# sheet6_power_supply.net
KiCad netlist of a schematic drawn in Altium Designer
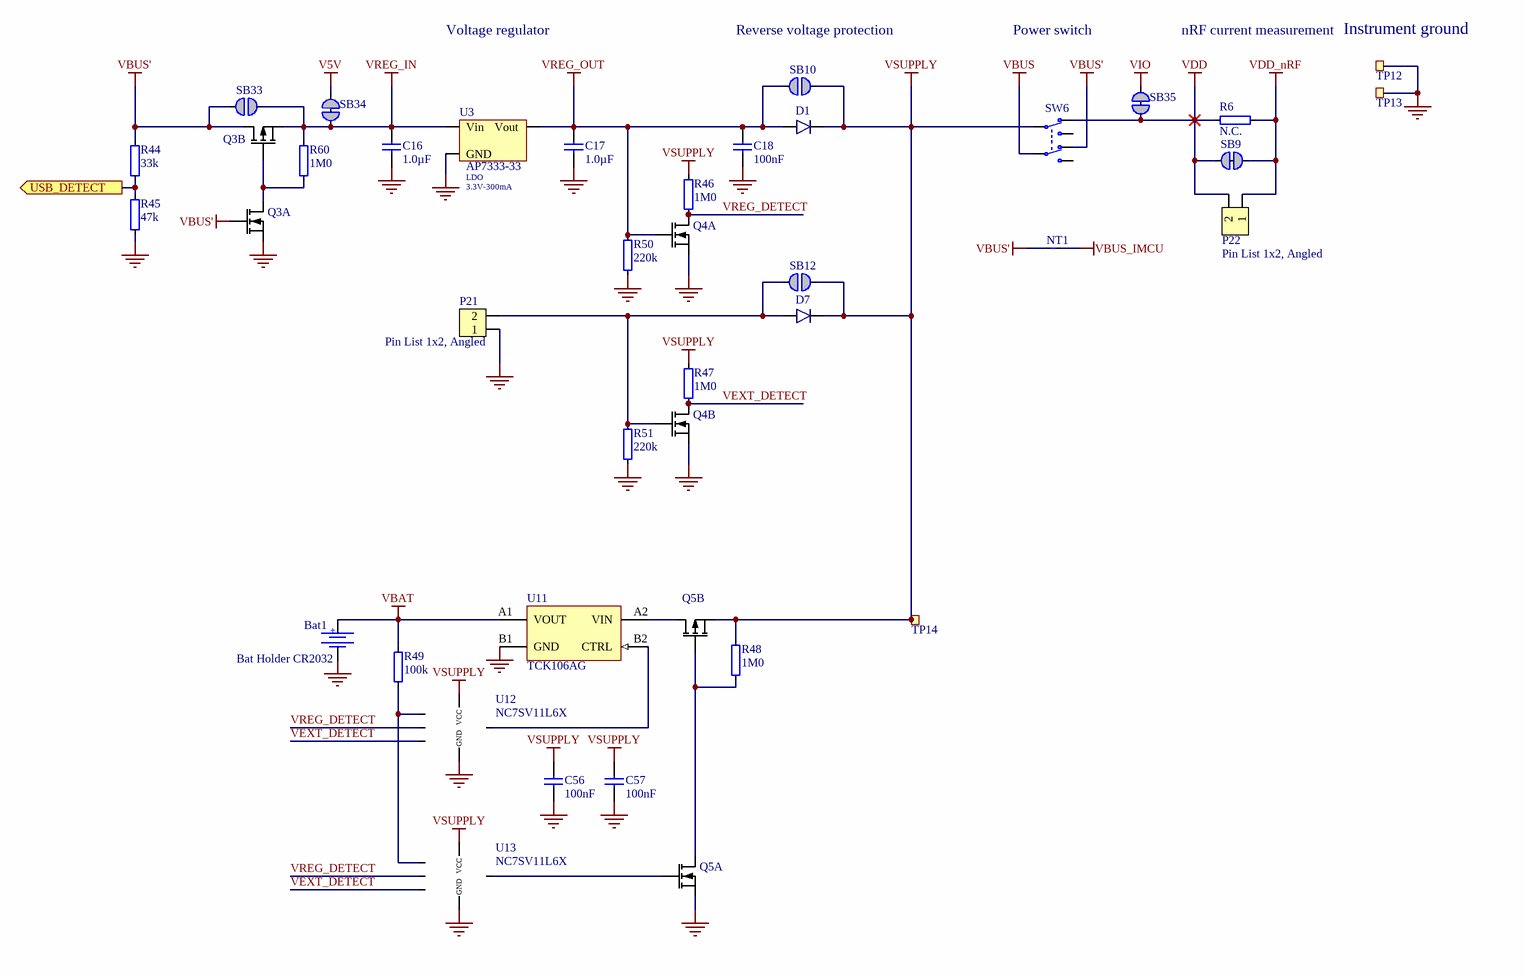
[diagram p0: sheet6_power_supply.SchDoc]

(export (version "E")
  (design (tool "Eeschema 10.0.6"))
  (components
    (comp (ref "Bat1")
      (value "Bat Holder CR2032")
      (footprint "L-KLS5-CR2032-23-B1")
      (description "Bat Holder CR2032 SMD")
      (fields
        (field (name "PART NUMBER") "Bat Holder L-KLS5-CR2032-23-B1")
        (field (name "MANUFACTURER") "KLS Electronic")
        (field (name "AUTHOR") "rsk")
      )
      (libsource (lib "AltiumLib") (part "Battery"))
    )
    (comp (ref "C16")
      (value "1.0µF")
      (footprint "CAPC1608X06L")
      (description "Capacitor, X7R, ±10%")
      (fields
        (field (name "PART NUMBER") "C0603-1µ0")
        (field (name "MANUFACTURER") "N.A.")
        (field (name "AUTHOR") "rsk")
      )
      (libsource (lib "AltiumLib") (part "CAP"))
    )
    (comp (ref "C17")
      (value "1.0µF")
      (footprint "CAPC1608X06L")
      (description "Capacitor, X7R, ±10%")
      (fields
        (field (name "PART NUMBER") "C0603-1µ0")
        (field (name "MANUFACTURER") "N.A.")
        (field (name "AUTHOR") "rsk")
      )
      (libsource (lib "AltiumLib") (part "CAP"))
    )
    (comp (ref "C18")
      (value "100nF")
      (footprint "CAPC1005X04L")
      (description "Capacitor, X7R, ±10%")
      (fields
        (field (name "PART NUMBER") "C0402-100n")
        (field (name "MANUFACTURER") "N.A.")
        (field (name "AUTHOR") "rsk")
      )
      (libsource (lib "AltiumLib") (part "CAP"))
    )
    (comp (ref "C56")
      (value "100nF")
      (footprint "CAPC0603X03L_C")
      (description "Capacitor, X5R, ±10%")
      (fields
        (field (name "PART NUMBER") "C0201-100n")
        (field (name "MANUFACTURER") "N.A.")
        (field (name "AUTHOR") "rsk")
      )
      (libsource (lib "AltiumLib") (part "CAP"))
    )
    (comp (ref "C57")
      (value "100nF")
      (footprint "CAPC0603X03L_C")
      (description "Capacitor, X5R, ±10%")
      (fields
        (field (name "PART NUMBER") "C0201-100n")
        (field (name "MANUFACTURER") "N.A.")
        (field (name "AUTHOR") "rsk")
      )
      (libsource (lib "AltiumLib") (part "CAP"))
    )
    (comp (ref "D1")
      (value "NSR0620P2T5G")
      (footprint "SODFL100X40-2N")
      (description "20V schottky barrier diode, Vf 350 mV @ 100 mA, Ir 2.0 µA @ 10 V, If 500 mA")
      (fields (field (name "MANUFACTURER") "ON Semiconductor") (field (name "AUTHOR") "rsk"))
      (libsource (lib "AltiumLib") (part "D{colon}DIODE_2PIN"))
    )
    (comp (ref "D7")
      (value "NSR0620P2T5G")
      (footprint "SODFL100X40-2N")
      (description "20V schottky barrier diode, Vf 350 mV @ 100 mA, Ir 2.0 µA @ 10 V, If 500 mA")
      (fields (field (name "MANUFACTURER") "ON Semiconductor") (field (name "AUTHOR") "rsk"))
      (libsource (lib "AltiumLib") (part "D{colon}DIODE_2PIN"))
    )
    (comp (ref "NT1")
      (value "NetTie_200um")
      (footprint "NetTie_200um")
      (description "Net Tie")
      (fields
        (field (name "PART NUMBER") "NetTie 0.2mm")
        (field (name "MANUFACTURER") "N.A.")
        (field (name "AUTHOR") "rsk")
      )
      (libsource (lib "AltiumLib") (part "NetTie"))
    )
    (comp (ref "P21")
      (value "Pin List 1x2, Angled")
      (footprint "LIST_ANG_1x2-SMD-2.54MM")
      (description "Pin List 1x2, 2.54mm (100mil), Right Angled, SMD")
      (fields
        (field (name "PART NUMBER") "Pin List Ang 1x2 SMD, 2.54mm")
        (field (name "MANUFACTURER") "W-CON")
        (field (name "AUTHOR") "rsk")
      )
      (libsource (lib "") (part "CONN-2_1"))
    )
    (comp (ref "P22")
      (value "Pin List 1x2, Angled")
      (footprint "LIST_ANG_1x2-SMD-2.54MM")
      (description "Pin List 1x2, 2.54mm (100mil), Right Angled, SMD")
      (fields
        (field (name "PART NUMBER") "Pin List Ang 1x2 SMD, 2.54mm")
        (field (name "MANUFACTURER") "W-CON")
        (field (name "AUTHOR") "rsk")
      )
      (libsource (lib "AltiumLib") (part "CONN-2"))
    )
    (comp (ref "Q3")
      (value "TSM2537CQ RFG")
      (footprint "DFN65P200X200X80_HS-6N")
      (description "Dual N & P Ch MOFET, 11.6A/9A, 90mOhm max, 6.25W")
      (fields (field (name "MANUFACTURER") "Taiwan Semiconductor") (field (name "AUTHOR") "rsk"))
      (libsource (lib "AltiumLib") (part "T{colon}FET-N/P-DUAL"))
    )
    (comp (ref "Q4")
      (value "TSM250N02DCQ RFG")
      (footprint "DFN65P200X200X80_HS-6N")
      (description "Dual N Ch MOFET, 5.8A, 55mOhm max, 620mW")
      (fields (field (name "MANUFACTURER") "Taiwan Semiconductor") (field (name "AUTHOR") "rsk"))
      (libsource (lib "AltiumLib") (part "T{colon}FET-N-DUAL"))
    )
    (comp (ref "Q5")
      (value "TSM2537CQ RFG")
      (footprint "DFN65P200X200X80_HS-6N")
      (description "Dual N & P Ch MOFET, 11.6A/9A, 90mOhm max, 6.25W")
      (fields (field (name "MANUFACTURER") "Taiwan Semiconductor") (field (name "AUTHOR") "rsk"))
      (libsource (lib "AltiumLib") (part "T{colon}FET-N/P-DUAL"))
    )
    (comp (ref "R6")
      (value "N.C.")
      (footprint "RESC1005X04L_NC")
      (description "Not mounted")
      (fields
        (field (name "PART NUMBER") "R0402-N.C.")
        (field (name "MANUFACTURER") "N.A.")
        (field (name "AUTHOR") "rsk")
      )
      (libsource (lib "AltiumLib") (part "RES"))
    )
    (comp (ref "R44")
      (value "33k")
      (footprint "RESC0603X03L_C")
      (description "Resistor, ±1%, 0.05W")
      (fields
        (field (name "PART NUMBER") "R0201-33k")
        (field (name "MANUFACTURER") "N.A.")
        (field (name "AUTHOR") "rsk")
      )
      (libsource (lib "AltiumLib") (part "RES"))
    )
    (comp (ref "R45")
      (value "47k")
      (footprint "RESC0603X03L_C")
      (description "Resistor, ±1%, 0.05W")
      (fields
        (field (name "PART NUMBER") "R0201-47k")
        (field (name "MANUFACTURER") "N.A.")
        (field (name "AUTHOR") "rsk")
      )
      (libsource (lib "AltiumLib") (part "RES"))
    )
    (comp (ref "R46")
      (value "1M0")
      (footprint "RESC0603X03L_C")
      (description "Resistor, ±1%, 0.05W")
      (fields
        (field (name "PART NUMBER") "R0201-1M0")
        (field (name "MANUFACTURER") "N.A.")
        (field (name "AUTHOR") "rsk")
      )
      (libsource (lib "AltiumLib") (part "RES"))
    )
    (comp (ref "R47")
      (value "1M0")
      (footprint "RESC0603X03L_C")
      (description "Resistor, ±1%, 0.05W")
      (fields
        (field (name "PART NUMBER") "R0201-1M0")
        (field (name "MANUFACTURER") "N.A.")
        (field (name "AUTHOR") "rsk")
      )
      (libsource (lib "AltiumLib") (part "RES"))
    )
    (comp (ref "R48")
      (value "1M0")
      (footprint "RESC0603X03L_C")
      (description "Resistor, ±1%, 0.05W")
      (fields
        (field (name "PART NUMBER") "R0201-1M0")
        (field (name "MANUFACTURER") "N.A.")
        (field (name "AUTHOR") "rsk")
      )
      (libsource (lib "AltiumLib") (part "RES"))
    )
    (comp (ref "R49")
      (value "100k")
      (footprint "RESC0603X03L_C")
      (description "Resistor, ±1%, 0.05W")
      (fields
        (field (name "PART NUMBER") "R0201-100k")
        (field (name "MANUFACTURER") "N.A.")
        (field (name "AUTHOR") "rsk")
      )
      (libsource (lib "AltiumLib") (part "RES"))
    )
    (comp (ref "R50")
      (value "220k")
      (footprint "RESC0603X03L_C")
      (description "Resistor, ±1%, 0.05W")
      (fields
        (field (name "PART NUMBER") "R0201-220k")
        (field (name "MANUFACTURER") "N.A.")
        (field (name "AUTHOR") "rsk")
      )
      (libsource (lib "AltiumLib") (part "RES"))
    )
    (comp (ref "R51")
      (value "220k")
      (footprint "RESC0603X03L_C")
      (description "Resistor, ±1%, 0.05W")
      (fields
        (field (name "PART NUMBER") "R0201-220k")
        (field (name "MANUFACTURER") "N.A.")
        (field (name "AUTHOR") "rsk")
      )
      (libsource (lib "AltiumLib") (part "RES"))
    )
    (comp (ref "R60")
      (value "1M0")
      (footprint "RESC0603X03L_C")
      (description "Resistor, ±1%, 0.05W")
      (fields
        (field (name "PART NUMBER") "R0201-1M0")
        (field (name "MANUFACTURER") "N.A.")
        (field (name "AUTHOR") "rsk")
      )
      (libsource (lib "AltiumLib") (part "RES"))
    )
    (comp (ref "SB9")
      (value "Solderbridge")
      (footprint "Solderbridge_Shorted")
      (description "Shorted Solderbridge")
      (fields
        (field (name "PART NUMBER") "Solderbridge Shorted")
        (field (name "MANUFACTURER") "N.A.")
        (field (name "AUTHOR") "rsk")
      )
      (libsource (lib "AltiumLib") (part "SOLDERBRIDGE_SHORTED"))
    )
    (comp (ref "SB10")
      (value "Solderbridge")
      (footprint "Solderbridge")
      (fields (field (name "MANUFACTURER") "N.A.") (field (name "AUTHOR") "rsk"))
      (libsource (lib "AltiumLib") (part "SOLDERBRIDGE"))
    )
    (comp (ref "SB12")
      (value "Solderbridge")
      (footprint "Solderbridge")
      (fields (field (name "MANUFACTURER") "N.A.") (field (name "AUTHOR") "rsk"))
      (libsource (lib "AltiumLib") (part "SOLDERBRIDGE"))
    )
    (comp (ref "SB33")
      (value "Solderbridge")
      (footprint "Solderbridge")
      (fields (field (name "MANUFACTURER") "N.A.") (field (name "AUTHOR") "rsk"))
      (libsource (lib "AltiumLib") (part "SOLDERBRIDGE"))
    )
    (comp (ref "SB34")
      (value "Solderbridge")
      (footprint "Solderbridge_Shorted")
      (description "Shorted Solderbridge")
      (fields
        (field (name "PART NUMBER") "Solderbridge Shorted")
        (field (name "MANUFACTURER") "N.A.")
        (field (name "AUTHOR") "rsk")
      )
      (libsource (lib "AltiumLib") (part "SOLDERBRIDGE_SHORTED"))
    )
    (comp (ref "SB35")
      (value "Solderbridge")
      (footprint "Solderbridge_Shorted_Power")
      (description "Shorted Solderbridge Power")
      (fields
        (field (name "PART NUMBER") "Solderbridge Shorted Power")
        (field (name "MANUFACTURER") "N.A.")
        (field (name "AUTHOR") "rsk")
      )
      (libsource (lib "AltiumLib") (part "SOLDERBRIDGE_SHORTED"))
    )
    (comp (ref "SW6")
      (value "MK-22D14-G2")
      (footprint "MK-22D14-G2")
      (description "Slide Switch DPDT")
      (fields (field (name "MANUFACTURER") "HUA-JIE CORP.") (field (name "AUTHOR") "rsk"))
      (libsource (lib "AltiumLib") (part "SW-DPDT"))
    )
    (comp (ref "TP12")
      (value "TP")
      (footprint "TESTPAD-TH")
      (description "Testpoint, through hole")
      (fields
        (field (name "PART NUMBER") "Testpoint TH")
        (field (name "MANUFACTURER") "N.A.")
        (field (name "AUTHOR") "rsk")
      )
      (libsource (lib "AltiumLib") (part "TESTPAD"))
    )
    (comp (ref "TP13")
      (value "TP")
      (footprint "TESTPAD-TH")
      (description "Testpoint, through hole")
      (fields
        (field (name "PART NUMBER") "Testpoint TH")
        (field (name "MANUFACTURER") "N.A.")
        (field (name "AUTHOR") "rsk")
      )
      (libsource (lib "AltiumLib") (part "TESTPAD"))
    )
    (comp (ref "TP14")
      (value "Ø1.0mm,SMD")
      (footprint "TP_SMD_D1.0mm")
      (description "1.0mm circular SMD testpad")
      (fields
        (field (name "PART NUMBER") "TP_SMD_Ø1.0MM")
        (field (name "MANUFACTURER") "Nordic Semiconductor")
        (field (name "AUTHOR") "rsk")
      )
      (libsource (lib "") (part "TESTPAD_1"))
    )
    (comp (ref "U3")
      (value "AP7333-33SAG-7")
      (footprint "SOT-23A")
      (description "300mA, Low Quiescent Current, Fast Transient Low Dropout Linear Regulator")
      (fields (field (name "MANUFACTURER") "Diodes Incorporated") (field (name "AUTHOR") "rsk"))
      (libsource (lib "AltiumLib") (part "AP7333-XXSAG"))
    )
    (comp (ref "U11")
      (value "TCK106AG")
      (footprint "BGA4C40P2X2_76X76X62")
      (description "1.0 A Load Switch IC with Slew Rate Control Driver in Ultra Small Package")
      (fields
        (field (name "MANUFACTURER") "Toshiba")
        (field (name "MANUFACTURER PART NUMBER") "TCK106AG,LF")
        (field (name "AUTHOR") "rsk")
      )
      (libsource (lib "AltiumLib") (part "TCK106AG"))
    )
    (comp (ref "U12")
      (value "NC7SV11L6X")
      (footprint "DFN1410-6N")
      (description "Single 3-input AND gate")
      (fields (field (name "MANUFACTURER") "ON Semiconductor") (field (name "AUTHOR") "rsk"))
      (libsource (lib "AltiumLib") (part "1G11"))
    )
    (comp (ref "U13")
      (value "NC7SV11L6X")
      (footprint "DFN1410-6N")
      (description "Single 3-input AND gate")
      (fields (field (name "MANUFACTURER") "ON Semiconductor") (field (name "AUTHOR") "rsk"))
      (libsource (lib "AltiumLib") (part "1G11"))
    )
  )
  (nets
    (net (code "1") (name "/USB_DETECT") (class "Default")
      (node (ref "R44") (pin "2") (pinfunction "2_2") (pintype "passive"))
      (node (ref "R45") (pin "1") (pinfunction "1_1") (pintype "passive"))
    )
    (net (code "2") (name "/VEXT_DETECT") (class "Default")
      (node (ref "Q4") (pin "3") (pinfunction "D2_3") (pintype "passive"))
      (node (ref "R47") (pin "2") (pinfunction "2_2") (pintype "passive"))
      (node (ref "U12") (pin "6") (pinfunction "C_6") (pintype "passive"))
      (node (ref "U13") (pin "6") (pinfunction "C_6") (pintype "passive"))
    )
    (net (code "3") (name "/VREG_DETECT") (class "Default")
      (node (ref "Q4") (pin "6") (pinfunction "D1_6") (pintype "passive"))
      (node (ref "R46") (pin "2") (pinfunction "2_2") (pintype "passive"))
      (node (ref "U12") (pin "3") (pinfunction "B_3") (pintype "passive"))
      (node (ref "U13") (pin "3") (pinfunction "B_3") (pintype "passive"))
    )
    (net (code "4") (name "GND") (class "Default")
      (node (ref "Bat1") (pin "2") (pintype "passive"))
      (node (ref "C16") (pin "1") (pinfunction "1_1") (pintype "passive"))
      (node (ref "C17") (pin "1") (pinfunction "1_1") (pintype "passive"))
      (node (ref "C18") (pin "1") (pinfunction "1_1") (pintype "passive"))
      (node (ref "C56") (pin "1") (pinfunction "1_1") (pintype "passive"))
      (node (ref "C57") (pin "1") (pinfunction "1_1") (pintype "passive"))
      (node (ref "P21") (pin "1") (pinfunction "1_1") (pintype "passive"))
      (node (ref "Q3") (pin "1") (pinfunction "S1_1") (pintype "passive"))
      (node (ref "Q4") (pin "1") (pinfunction "S1_1") (pintype "passive"))
      (node (ref "Q4") (pin "4") (pinfunction "S2_4") (pintype "passive"))
      (node (ref "Q5") (pin "1") (pinfunction "S1_1") (pintype "passive"))
      (node (ref "R45") (pin "2") (pinfunction "2_2") (pintype "passive"))
      (node (ref "R50") (pin "2") (pinfunction "2_2") (pintype "passive"))
      (node (ref "R51") (pin "2") (pinfunction "2_2") (pintype "passive"))
      (node (ref "TP12") (pin "1") (pinfunction "1_1") (pintype "passive"))
      (node (ref "TP13") (pin "1") (pinfunction "1_1") (pintype "passive"))
      (node (ref "U11") (pin "B1") (pinfunction "GND_B1") (pintype "power_in"))
      (node (ref "U12") (pin "2") (pinfunction "GND_2") (pintype "power_in"))
      (node (ref "U13") (pin "2") (pinfunction "GND_2") (pintype "power_in"))
      (node (ref "U3") (pin "3") (pinfunction "GND_3") (pintype "passive"))
    )
    (net (code "5") (name "Net-(D7-A)") (class "Default")
      (node (ref "D7") (pin "2") (pinfunction "A_2") (pintype "passive"))
      (node (ref "P21") (pin "2") (pinfunction "2_2") (pintype "passive"))
      (node (ref "Q4") (pin "5") (pinfunction "G2_5") (pintype "passive"))
      (node (ref "R51") (pin "1") (pinfunction "1_1") (pintype "passive"))
      (node (ref "SB12") (pin "2") (pinfunction "1_2") (pintype "passive"))
    )
    (net (code "6") (name "Net-(Q3A-D1)") (class "Default")
      (node (ref "Q3") (pin "5") (pinfunction "G2_5") (pintype "passive"))
      (node (ref "Q3") (pin "6") (pinfunction "D1_6") (pintype "passive"))
      (node (ref "R60") (pin "2") (pinfunction "2_2") (pintype "passive"))
    )
    (net (code "7") (name "Net-(Q5A-D1)") (class "Default")
      (node (ref "Q5") (pin "5") (pinfunction "G2_5") (pintype "passive"))
      (node (ref "Q5") (pin "6") (pinfunction "D1_6") (pintype "passive"))
      (node (ref "R48") (pin "2") (pinfunction "2_2") (pintype "passive"))
    )
    (net (code "8") (name "Net-(Q5A-G1)") (class "Default")
      (node (ref "Q5") (pin "2") (pinfunction "G1_2") (pintype "passive"))
      (node (ref "U13") (pin "4") (pinfunction "Y_4") (pintype "passive"))
    )
    (net (code "9") (name "Net-(Q5B-D2)") (class "Default")
      (node (ref "Q5") (pin "3") (pinfunction "D2_3") (pintype "passive"))
      (node (ref "U11") (pin "A2") (pinfunction "VIN_A2") (pintype "power_in"))
    )
    (net (code "10") (name "Net-(U11-CTRL)") (class "Default")
      (node (ref "U11") (pin "B2") (pinfunction "CTRL_B2") (pintype "input"))
      (node (ref "U12") (pin "4") (pinfunction "Y_4") (pintype "passive"))
    )
    (net (code "11") (name "Net-(U12-A)") (class "Default")
      (node (ref "R49") (pin "2") (pinfunction "2_2") (pintype "passive"))
      (node (ref "U12") (pin "1") (pinfunction "A_1") (pintype "passive"))
      (node (ref "U13") (pin "1") (pinfunction "A_1") (pintype "passive"))
    )
    (net (code "12") (name "V5V") (class "Default")
      (node (ref "SB34") (pin "1") (pinfunction "0_1") (pintype "passive"))
    )
    (net (code "13") (name "VBAT") (class "Default")
      (node (ref "Bat1") (pin "1") (pintype "passive"))
      (node (ref "R49") (pin "1") (pinfunction "1_1") (pintype "passive"))
      (node (ref "U11") (pin "A1") (pinfunction "VOUT_A1") (pintype "power_in"))
    )
    (net (code "14") (name "VBUS") (class "Default")
      (node (ref "SW6") (pin "5") (pinfunction "COM-2_5") (pintype "passive"))
    )
    (net (code "15") (name "VBUS'") (class "Default")
      (node (ref "NT1") (pin "1") (pinfunction "1_1") (pintype "passive"))
      (node (ref "Q3") (pin "2") (pinfunction "G1_2") (pintype "passive"))
      (node (ref "Q3") (pin "3") (pinfunction "D2_3") (pintype "passive"))
      (node (ref "R44") (pin "1") (pinfunction "1_1") (pintype "passive"))
      (node (ref "SB33") (pin "2") (pinfunction "1_2") (pintype "passive"))
      (node (ref "SW6") (pin "6") (pinfunction "N.C-2_6") (pintype "passive"))
    )
    (net (code "16") (name "VBUS_IMCU") (class "Default")
      (node (ref "NT1") (pin "2") (pinfunction "2_2") (pintype "passive"))
    )
    (net (code "17") (name "VDD") (class "Default")
      (node (ref "P22") (pin "2") (pinfunction "2_2") (pintype "passive"))
      (node (ref "R6") (pin "1") (pinfunction "1_1") (pintype "passive"))
      (node (ref "SB35") (pin "2") (pinfunction "1_2") (pintype "passive"))
      (node (ref "SB9") (pin "2") (pinfunction "1_2") (pintype "passive"))
      (node (ref "SW6") (pin "3") (pinfunction "N.C-1_3") (pintype "passive"))
    )
    (net (code "18") (name "VDD_nRF") (class "Default")
      (node (ref "P22") (pin "1") (pinfunction "1_1") (pintype "passive"))
      (node (ref "R6") (pin "2") (pinfunction "2_2") (pintype "passive"))
      (node (ref "SB9") (pin "1") (pinfunction "0_1") (pintype "passive"))
    )
    (net (code "19") (name "VIO") (class "Default")
      (node (ref "SB35") (pin "1") (pinfunction "0_1") (pintype "passive"))
    )
    (net (code "20") (name "VREG_IN") (class "Default")
      (node (ref "C16") (pin "2") (pinfunction "2_2") (pintype "passive"))
      (node (ref "Q3") (pin "4") (pinfunction "S2_4") (pintype "passive"))
      (node (ref "R60") (pin "1") (pinfunction "1_1") (pintype "passive"))
      (node (ref "SB33") (pin "1") (pinfunction "0_1") (pintype "passive"))
      (node (ref "SB34") (pin "2") (pinfunction "1_2") (pintype "passive"))
      (node (ref "U3") (pin "1") (pinfunction "Vin_1") (pintype "passive"))
    )
    (net (code "21") (name "VREG_OUT") (class "Default")
      (node (ref "C17") (pin "2") (pinfunction "2_2") (pintype "passive"))
      (node (ref "C18") (pin "2") (pinfunction "2_2") (pintype "passive"))
      (node (ref "D1") (pin "2") (pinfunction "A_2") (pintype "passive"))
      (node (ref "Q4") (pin "2") (pinfunction "G1_2") (pintype "passive"))
      (node (ref "R50") (pin "1") (pinfunction "1_1") (pintype "passive"))
      (node (ref "SB10") (pin "2") (pinfunction "1_2") (pintype "passive"))
      (node (ref "U3") (pin "2") (pinfunction "Vout_2") (pintype "passive"))
    )
    (net (code "22") (name "VSUPPLY") (class "Default")
      (node (ref "C56") (pin "2") (pinfunction "2_2") (pintype "passive"))
      (node (ref "C57") (pin "2") (pinfunction "2_2") (pintype "passive"))
      (node (ref "D1") (pin "1") (pinfunction "C_1") (pintype "passive"))
      (node (ref "D7") (pin "1") (pinfunction "C_1") (pintype "passive"))
      (node (ref "Q5") (pin "4") (pinfunction "S2_4") (pintype "passive"))
      (node (ref "R46") (pin "1") (pinfunction "1_1") (pintype "passive"))
      (node (ref "R47") (pin "1") (pinfunction "1_1") (pintype "passive"))
      (node (ref "R48") (pin "1") (pinfunction "1_1") (pintype "passive"))
      (node (ref "SB10") (pin "1") (pinfunction "0_1") (pintype "passive"))
      (node (ref "SB12") (pin "1") (pinfunction "0_1") (pintype "passive"))
      (node (ref "SW6") (pin "2") (pinfunction "COM-1_2") (pintype "passive"))
      (node (ref "TP14") (pin "1") (pinfunction "1_1") (pintype "passive"))
      (node (ref "U12") (pin "5") (pinfunction "VCC_5") (pintype "power_in"))
      (node (ref "U13") (pin "5") (pinfunction "VCC_5") (pintype "power_in"))
    )
    (net (code "23") (name "unconnected-(SW6-N.O-1-Pad1)") (class "Default")
      (node (ref "SW6") (pin "1") (pinfunction "N.O-1_1") (pintype "passive"))
    )
    (net (code "24") (name "unconnected-(SW6-N.O-2-Pad4)") (class "Default")
      (node (ref "SW6") (pin "4") (pinfunction "N.O-2_4") (pintype "passive"))
    )
  )
)
